# 1.net
KiCad netlist of a schematic drawn in EAGLE
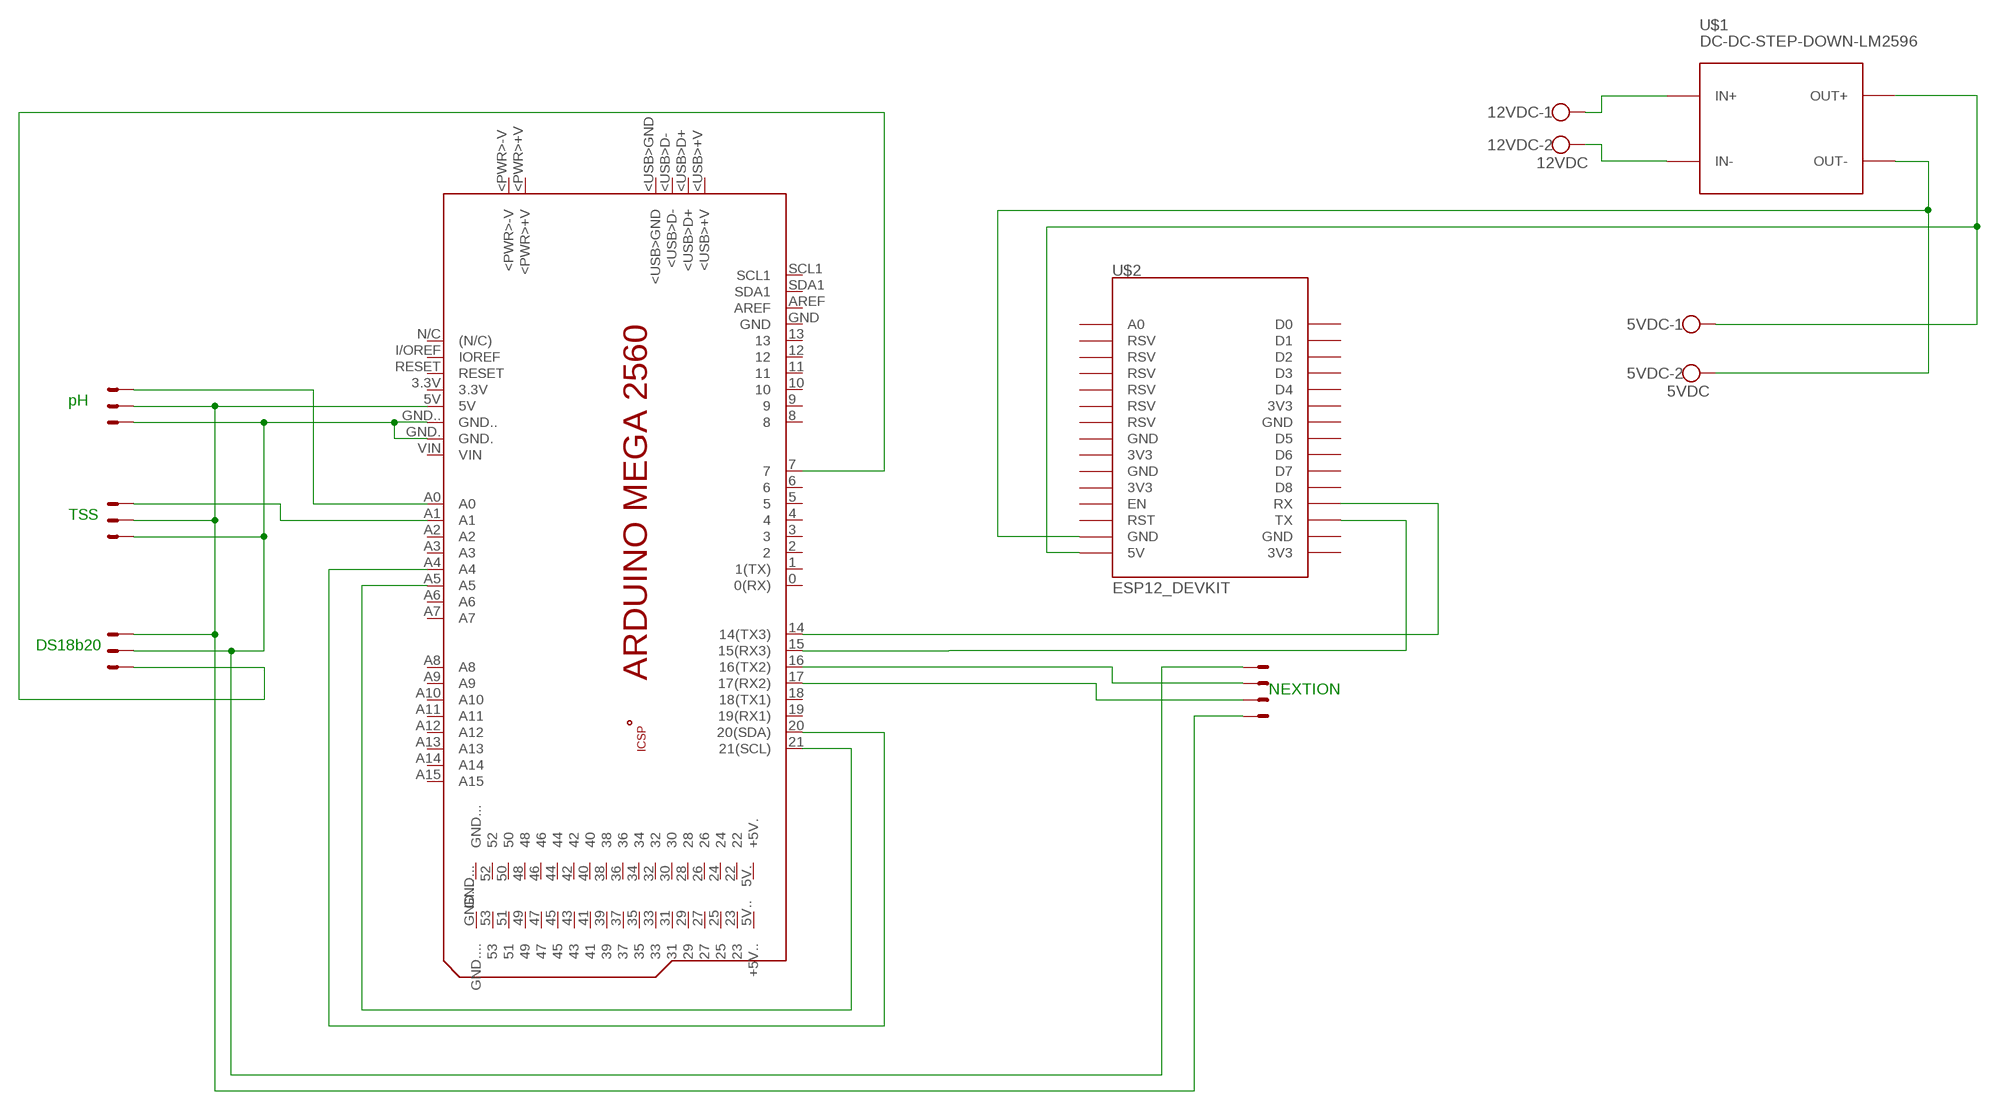
[diagram p0: schematic, sheet 1]

(export (version "E")
  (design (tool "Eeschema 10.0.6"))
  (components
    (comp (ref "5VDC")
      (value "5VDC")
      (footprint "eagle-import:W237-102")
      (fields (field (name "MPN") "237-102"))
      (libsource (lib "eagle-import") (part "W237-102"))
    )
    (comp (ref "12VDC")
      (value "12VDC")
      (footprint "eagle-import:W237-102")
      (fields (field (name "MPN") "237-102"))
      (libsource (lib "eagle-import") (part "W237-102"))
    )
    (comp (ref "A0")
      (value "22-23-2031")
      (footprint "eagle-import:22-23-2031")
      (fields (field (name "MF") "MOLEX"))
      (libsource (lib "eagle-import") (part "22-23-2031"))
    )
    (comp (ref "PCB1")
      (value "ARDUINO_MEGA2560")
      (footprint "eagle-import:ARDUINO_MEGA2560")
      (libsource (lib "eagle-import") (part "ARDUINO_MEGA2560"))
    )
    (comp (ref "U$1")
      (value "DC-DC-STEP-DOWN-LM2596")
      (footprint "eagle-import:DC-DC-STEP-DOWN-LM2596")
      (libsource (lib "eagle-import") (part "DC-DC-STEP-DOWN-LM2596"))
    )
    (comp (ref "U$2")
      (value "ESP12_DEVKIT")
      (footprint "eagle-import:ESP12_DEVKIT")
      (libsource (lib "eagle-import") (part "ESP12_DEVKIT"))
    )
    (comp (ref "X1")
      (value "22-23-2041")
      (footprint "eagle-import:22-23-2041")
      (fields (field (name "MF") "MOLEX"))
      (libsource (lib "eagle-import") (part "22-23-2041"))
    )
    (comp (ref "X2")
      (value "22-23-2031")
      (footprint "eagle-import:22-23-2031")
      (fields (field (name "MF") "MOLEX"))
      (libsource (lib "eagle-import") (part "22-23-2031"))
    )
    (comp (ref "X3")
      (value "22-23-2031")
      (footprint "eagle-import:22-23-2031")
      (fields (field (name "MF") "MOLEX"))
      (libsource (lib "eagle-import") (part "22-23-2031"))
    )
  )
  (nets
    (net (code "1") (name "Net-(5VDCA-KL)") (class "Default")
      (node (ref "5VDC") (pin "1") (pinfunction "KL_1") (pintype "passive"))
      (node (ref "U$1") (pin "OUT+") (pinfunction "OUT+_OUT+") (pintype "bidirectional"))
      (node (ref "U$2") (pin "5V") (pinfunction "5V_5V") (pintype "bidirectional"))
    )
    (net (code "2") (name "Net-(5VDCB-KL)") (class "Default")
      (node (ref "5VDC") (pin "2") (pinfunction "KL_2") (pintype "passive"))
      (node (ref "U$1") (pin "OUT-") (pinfunction "OUT-_OUT-") (pintype "bidirectional"))
      (node (ref "U$2") (pin "GND@1") (pinfunction "GND_GND@1") (pintype "bidirectional"))
    )
    (net (code "3") (name "Net-(12VDCA-KL)") (class "Default")
      (node (ref "12VDC") (pin "1") (pinfunction "KL_1") (pintype "passive"))
      (node (ref "U$1") (pin "IN+") (pinfunction "IN+_IN+") (pintype "bidirectional"))
    )
    (net (code "4") (name "Net-(12VDCB-KL)") (class "Default")
      (node (ref "12VDC") (pin "2") (pinfunction "KL_2") (pintype "passive"))
      (node (ref "U$1") (pin "IN-") (pinfunction "IN-_IN-") (pintype "bidirectional"))
    )
    (net (code "5") (name "Net-(A0A-S)") (class "Default")
      (node (ref "A0") (pin "1") (pinfunction "S_1") (pintype "passive"))
      (node (ref "PCB1") (pin "GND.") (pinfunction "GND._GND.") (pintype "bidirectional"))
      (node (ref "PCB1") (pin "GND..") (pinfunction "GND.._GND..") (pintype "bidirectional"))
      (node (ref "X1") (pin "1") (pinfunction "S_1") (pintype "passive"))
      (node (ref "X2") (pin "1") (pinfunction "S_1") (pintype "passive"))
      (node (ref "X3") (pin "2") (pinfunction "S_2") (pintype "passive"))
    )
    (net (code "6") (name "Net-(A0B-S)") (class "Default")
      (node (ref "A0") (pin "2") (pinfunction "S_2") (pintype "passive"))
      (node (ref "PCB1") (pin "5V") (pinfunction "5V_5V") (pintype "bidirectional"))
      (node (ref "X1") (pin "4") (pinfunction "S_4") (pintype "passive"))
      (node (ref "X2") (pin "2") (pinfunction "S_2") (pintype "passive"))
      (node (ref "X3") (pin "3") (pinfunction "S_3") (pintype "passive"))
    )
    (net (code "7") (name "Net-(A0C-S)") (class "Default")
      (node (ref "A0") (pin "3") (pinfunction "S_3") (pintype "passive"))
      (node (ref "PCB1") (pin "A0") (pinfunction "A0_A0") (pintype "bidirectional"))
    )
    (net (code "8") (name "Net-(PCB1-14(TX3))") (class "Default")
      (node (ref "PCB1") (pin "14") (pinfunction "14(TX3)_14") (pintype "bidirectional"))
      (node (ref "U$2") (pin "RX") (pinfunction "RX_RX") (pintype "bidirectional"))
    )
    (net (code "9") (name "Net-(PCB1-15(RX3))") (class "Default")
      (node (ref "PCB1") (pin "15") (pinfunction "15(RX3)_15") (pintype "bidirectional"))
      (node (ref "U$2") (pin "TX") (pinfunction "TX_TX") (pintype "bidirectional"))
    )
    (net (code "10") (name "Net-(PCB1-16(TX2))") (class "Default")
      (node (ref "PCB1") (pin "16") (pinfunction "16(TX2)_16") (pintype "bidirectional"))
      (node (ref "X1") (pin "2") (pinfunction "S_2") (pintype "passive"))
    )
    (net (code "11") (name "Net-(PCB1-17(RX2))") (class "Default")
      (node (ref "PCB1") (pin "17") (pinfunction "17(RX2)_17") (pintype "bidirectional"))
      (node (ref "X1") (pin "3") (pinfunction "S_3") (pintype "passive"))
    )
    (net (code "12") (name "Net-(PCB1-20(SDA))") (class "Default")
      (node (ref "PCB1") (pin "20") (pinfunction "20(SDA)_20") (pintype "bidirectional"))
      (node (ref "PCB1") (pin "A4") (pinfunction "A4_A4") (pintype "bidirectional"))
    )
    (net (code "13") (name "Net-(PCB1-21(SCL))") (class "Default")
      (node (ref "PCB1") (pin "21") (pinfunction "21(SCL)_21") (pintype "bidirectional"))
      (node (ref "PCB1") (pin "A5") (pinfunction "A5_A5") (pintype "bidirectional"))
    )
    (net (code "14") (name "Net-(X2C-S)") (class "Default")
      (node (ref "PCB1") (pin "A1") (pinfunction "A1_A1") (pintype "bidirectional"))
      (node (ref "X2") (pin "3") (pinfunction "S_3") (pintype "passive"))
    )
    (net (code "15") (name "Net-(X3A-S)") (class "Default")
      (node (ref "PCB1") (pin "7") (pinfunction "7_7") (pintype "bidirectional"))
      (node (ref "X3") (pin "1") (pinfunction "S_1") (pintype "passive"))
    )
    (net (code "16") (name "unconnected-(PCB1-(N{slash}C)-PadN{slash}C)") (class "Default")
      (node (ref "PCB1") (pin "N/C") (pinfunction "(N/C)_N/C") (pintype "bidirectional"))
    )
    (net (code "17") (name "unconnected-(PCB1-+5V.-Pad5V.)") (class "Default")
      (node (ref "PCB1") (pin "5V.") (pinfunction "+5V._5V.") (pintype "bidirectional"))
    )
    (net (code "18") (name "unconnected-(PCB1-+5V..-Pad5V..)") (class "Default")
      (node (ref "PCB1") (pin "5V..") (pinfunction "+5V.._5V..") (pintype "bidirectional"))
    )
    (net (code "19") (name "unconnected-(PCB1-0(RX)-Pad0)") (class "Default")
      (node (ref "PCB1") (pin "0") (pinfunction "0(RX)_0") (pintype "bidirectional"))
    )
    (net (code "20") (name "unconnected-(PCB1-1(TX)-Pad1)") (class "Default")
      (node (ref "PCB1") (pin "1") (pinfunction "1(TX)_1") (pintype "bidirectional"))
    )
    (net (code "21") (name "unconnected-(PCB1-18(TX1)-Pad18)") (class "Default")
      (node (ref "PCB1") (pin "18") (pinfunction "18(TX1)_18") (pintype "bidirectional"))
    )
    (net (code "22") (name "unconnected-(PCB1-19(RX1)-Pad19)") (class "Default")
      (node (ref "PCB1") (pin "19") (pinfunction "19(RX1)_19") (pintype "bidirectional"))
    )
    (net (code "23") (name "unconnected-(PCB1-IOREF-PadI{slash}OREF)") (class "Default")
      (node (ref "PCB1") (pin "I/OREF") (pinfunction "IOREF_I/OREF") (pintype "bidirectional"))
    )
    (net (code "24") (name "unconnected-(PCB1-Pad+5V_)") (class "Default")
      (node (ref "PCB1") (pin "+5V_") (pinfunction "+5V__+5V_") (pintype "bidirectional"))
    )
    (net (code "25") (name "unconnected-(PCB1-Pad2)") (class "Default")
      (node (ref "PCB1") (pin "2") (pinfunction "2_2") (pintype "bidirectional"))
    )
    (net (code "26") (name "unconnected-(PCB1-Pad3)") (class "Default")
      (node (ref "PCB1") (pin "3") (pinfunction "3_3") (pintype "bidirectional"))
    )
    (net (code "27") (name "unconnected-(PCB1-Pad3.3V)") (class "Default")
      (node (ref "PCB1") (pin "3.3V") (pinfunction "3.3V_3.3V") (pintype "bidirectional"))
    )
    (net (code "28") (name "unconnected-(PCB1-Pad4)") (class "Default")
      (node (ref "PCB1") (pin "4") (pinfunction "4_4") (pintype "bidirectional"))
    )
    (net (code "29") (name "unconnected-(PCB1-Pad5)") (class "Default")
      (node (ref "PCB1") (pin "5") (pinfunction "5_5") (pintype "bidirectional"))
    )
    (net (code "30") (name "unconnected-(PCB1-Pad6)") (class "Default")
      (node (ref "PCB1") (pin "6") (pinfunction "6_6") (pintype "bidirectional"))
    )
    (net (code "31") (name "unconnected-(PCB1-Pad8)") (class "Default")
      (node (ref "PCB1") (pin "8") (pinfunction "8_8") (pintype "bidirectional"))
    )
    (net (code "32") (name "unconnected-(PCB1-Pad9)") (class "Default")
      (node (ref "PCB1") (pin "9") (pinfunction "9_9") (pintype "bidirectional"))
    )
    (net (code "33") (name "unconnected-(PCB1-Pad10)") (class "Default")
      (node (ref "PCB1") (pin "10") (pinfunction "10_10") (pintype "bidirectional"))
    )
    (net (code "34") (name "unconnected-(PCB1-Pad11)") (class "Default")
      (node (ref "PCB1") (pin "11") (pinfunction "11_11") (pintype "bidirectional"))
    )
    (net (code "35") (name "unconnected-(PCB1-Pad12)") (class "Default")
      (node (ref "PCB1") (pin "12") (pinfunction "12_12") (pintype "bidirectional"))
    )
    (net (code "36") (name "unconnected-(PCB1-Pad13)") (class "Default")
      (node (ref "PCB1") (pin "13") (pinfunction "13_13") (pintype "bidirectional"))
    )
    (net (code "37") (name "unconnected-(PCB1-Pad22)") (class "Default")
      (node (ref "PCB1") (pin "22") (pinfunction "22_22") (pintype "bidirectional"))
    )
    (net (code "38") (name "unconnected-(PCB1-Pad23)") (class "Default")
      (node (ref "PCB1") (pin "23") (pinfunction "23_23") (pintype "bidirectional"))
    )
    (net (code "39") (name "unconnected-(PCB1-Pad24)") (class "Default")
      (node (ref "PCB1") (pin "24") (pinfunction "24_24") (pintype "bidirectional"))
    )
    (net (code "40") (name "unconnected-(PCB1-Pad25)") (class "Default")
      (node (ref "PCB1") (pin "25") (pinfunction "25_25") (pintype "bidirectional"))
    )
    (net (code "41") (name "unconnected-(PCB1-Pad26)") (class "Default")
      (node (ref "PCB1") (pin "26") (pinfunction "26_26") (pintype "bidirectional"))
    )
    (net (code "42") (name "unconnected-(PCB1-Pad27)") (class "Default")
      (node (ref "PCB1") (pin "27") (pinfunction "27_27") (pintype "bidirectional"))
    )
    (net (code "43") (name "unconnected-(PCB1-Pad28)") (class "Default")
      (node (ref "PCB1") (pin "28") (pinfunction "28_28") (pintype "bidirectional"))
    )
    (net (code "44") (name "unconnected-(PCB1-Pad29)") (class "Default")
      (node (ref "PCB1") (pin "29") (pinfunction "29_29") (pintype "bidirectional"))
    )
    (net (code "45") (name "unconnected-(PCB1-Pad30)") (class "Default")
      (node (ref "PCB1") (pin "30") (pinfunction "30_30") (pintype "bidirectional"))
    )
    (net (code "46") (name "unconnected-(PCB1-Pad31)") (class "Default")
      (node (ref "PCB1") (pin "31") (pinfunction "31_31") (pintype "bidirectional"))
    )
    (net (code "47") (name "unconnected-(PCB1-Pad32)") (class "Default")
      (node (ref "PCB1") (pin "32") (pinfunction "32_32") (pintype "bidirectional"))
    )
    (net (code "48") (name "unconnected-(PCB1-Pad33)") (class "Default")
      (node (ref "PCB1") (pin "33") (pinfunction "33_33") (pintype "bidirectional"))
    )
    (net (code "49") (name "unconnected-(PCB1-Pad34)") (class "Default")
      (node (ref "PCB1") (pin "34") (pinfunction "34_34") (pintype "bidirectional"))
    )
    (net (code "50") (name "unconnected-(PCB1-Pad35)") (class "Default")
      (node (ref "PCB1") (pin "35") (pinfunction "35_35") (pintype "bidirectional"))
    )
    (net (code "51") (name "unconnected-(PCB1-Pad36)") (class "Default")
      (node (ref "PCB1") (pin "36") (pinfunction "36_36") (pintype "bidirectional"))
    )
    (net (code "52") (name "unconnected-(PCB1-Pad37)") (class "Default")
      (node (ref "PCB1") (pin "37") (pinfunction "37_37") (pintype "bidirectional"))
    )
    (net (code "53") (name "unconnected-(PCB1-Pad38)") (class "Default")
      (node (ref "PCB1") (pin "38") (pinfunction "38_38") (pintype "bidirectional"))
    )
    (net (code "54") (name "unconnected-(PCB1-Pad39)") (class "Default")
      (node (ref "PCB1") (pin "39") (pinfunction "39_39") (pintype "bidirectional"))
    )
    (net (code "55") (name "unconnected-(PCB1-Pad40)") (class "Default")
      (node (ref "PCB1") (pin "40") (pinfunction "40_40") (pintype "bidirectional"))
    )
    (net (code "56") (name "unconnected-(PCB1-Pad41)") (class "Default")
      (node (ref "PCB1") (pin "41") (pinfunction "41_41") (pintype "bidirectional"))
    )
    (net (code "57") (name "unconnected-(PCB1-Pad42)") (class "Default")
      (node (ref "PCB1") (pin "42") (pinfunction "42_42") (pintype "bidirectional"))
    )
    (net (code "58") (name "unconnected-(PCB1-Pad43)") (class "Default")
      (node (ref "PCB1") (pin "43") (pinfunction "43_43") (pintype "bidirectional"))
    )
    (net (code "59") (name "unconnected-(PCB1-Pad44)") (class "Default")
      (node (ref "PCB1") (pin "44") (pinfunction "44_44") (pintype "bidirectional"))
    )
    (net (code "60") (name "unconnected-(PCB1-Pad45)") (class "Default")
      (node (ref "PCB1") (pin "45") (pinfunction "45_45") (pintype "bidirectional"))
    )
    (net (code "61") (name "unconnected-(PCB1-Pad46)") (class "Default")
      (node (ref "PCB1") (pin "46") (pinfunction "46_46") (pintype "bidirectional"))
    )
    (net (code "62") (name "unconnected-(PCB1-Pad47)") (class "Default")
      (node (ref "PCB1") (pin "47") (pinfunction "47_47") (pintype "bidirectional"))
    )
    (net (code "63") (name "unconnected-(PCB1-Pad48)") (class "Default")
      (node (ref "PCB1") (pin "48") (pinfunction "48_48") (pintype "bidirectional"))
    )
    (net (code "64") (name "unconnected-(PCB1-Pad49)") (class "Default")
      (node (ref "PCB1") (pin "49") (pinfunction "49_49") (pintype "bidirectional"))
    )
    (net (code "65") (name "unconnected-(PCB1-Pad50)") (class "Default")
      (node (ref "PCB1") (pin "50") (pinfunction "50_50") (pintype "bidirectional"))
    )
    (net (code "66") (name "unconnected-(PCB1-Pad51)") (class "Default")
      (node (ref "PCB1") (pin "51") (pinfunction "51_51") (pintype "bidirectional"))
    )
    (net (code "67") (name "unconnected-(PCB1-Pad52)") (class "Default")
      (node (ref "PCB1") (pin "52") (pinfunction "52_52") (pintype "bidirectional"))
    )
    (net (code "68") (name "unconnected-(PCB1-Pad53)") (class "Default")
      (node (ref "PCB1") (pin "53") (pinfunction "53_53") (pintype "bidirectional"))
    )
    (net (code "69") (name "unconnected-(PCB1-Pad<PWR>+V)") (class "Default")
      (node (ref "PCB1") (pin "<PWR>+V") (pinfunction "<PWR>+V_<PWR>+V") (pintype "no_connect"))
    )
    (net (code "70") (name "unconnected-(PCB1-Pad<PWR>-V)") (class "Default")
      (node (ref "PCB1") (pin "<PWR>-V") (pinfunction "<PWR>-V_<PWR>-V") (pintype "no_connect"))
    )
    (net (code "71") (name "unconnected-(PCB1-Pad<USB>+V)") (class "Default")
      (node (ref "PCB1") (pin "<USB>+V") (pinfunction "<USB>+V_<USB>+V") (pintype "no_connect"))
    )
    (net (code "72") (name "unconnected-(PCB1-Pad<USB>D+)") (class "Default")
      (node (ref "PCB1") (pin "<USB>D+") (pinfunction "<USB>D+_<USB>D+") (pintype "no_connect"))
    )
    (net (code "73") (name "unconnected-(PCB1-Pad<USB>D-)") (class "Default")
      (node (ref "PCB1") (pin "<USB>D-") (pinfunction "<USB>D-_<USB>D-") (pintype "no_connect"))
    )
    (net (code "74") (name "unconnected-(PCB1-Pad<USB>GND)") (class "Default")
      (node (ref "PCB1") (pin "<USB>GND") (pinfunction "<USB>GND_<USB>GND") (pintype "no_connect"))
    )
    (net (code "75") (name "unconnected-(PCB1-PadA2)") (class "Default")
      (node (ref "PCB1") (pin "A2") (pinfunction "A2_A2") (pintype "bidirectional"))
    )
    (net (code "76") (name "unconnected-(PCB1-PadA3)") (class "Default")
      (node (ref "PCB1") (pin "A3") (pinfunction "A3_A3") (pintype "bidirectional"))
    )
    (net (code "77") (name "unconnected-(PCB1-PadA6)") (class "Default")
      (node (ref "PCB1") (pin "A6") (pinfunction "A6_A6") (pintype "bidirectional"))
    )
    (net (code "78") (name "unconnected-(PCB1-PadA7)") (class "Default")
      (node (ref "PCB1") (pin "A7") (pinfunction "A7_A7") (pintype "bidirectional"))
    )
    (net (code "79") (name "unconnected-(PCB1-PadA8)") (class "Default")
      (node (ref "PCB1") (pin "A8") (pinfunction "A8_A8") (pintype "bidirectional"))
    )
    (net (code "80") (name "unconnected-(PCB1-PadA9)") (class "Default")
      (node (ref "PCB1") (pin "A9") (pinfunction "A9_A9") (pintype "bidirectional"))
    )
    (net (code "81") (name "unconnected-(PCB1-PadA10)") (class "Default")
      (node (ref "PCB1") (pin "A10") (pinfunction "A10_A10") (pintype "bidirectional"))
    )
    (net (code "82") (name "unconnected-(PCB1-PadA11)") (class "Default")
      (node (ref "PCB1") (pin "A11") (pinfunction "A11_A11") (pintype "bidirectional"))
    )
    (net (code "83") (name "unconnected-(PCB1-PadA12)") (class "Default")
      (node (ref "PCB1") (pin "A12") (pinfunction "A12_A12") (pintype "bidirectional"))
    )
    (net (code "84") (name "unconnected-(PCB1-PadA13)") (class "Default")
      (node (ref "PCB1") (pin "A13") (pinfunction "A13_A13") (pintype "bidirectional"))
    )
    (net (code "85") (name "unconnected-(PCB1-PadA14)") (class "Default")
      (node (ref "PCB1") (pin "A14") (pinfunction "A14_A14") (pintype "bidirectional"))
    )
    (net (code "86") (name "unconnected-(PCB1-PadA15)") (class "Default")
      (node (ref "PCB1") (pin "A15") (pinfunction "A15_A15") (pintype "bidirectional"))
    )
    (net (code "87") (name "unconnected-(PCB1-PadAREF)") (class "Default")
      (node (ref "PCB1") (pin "AREF") (pinfunction "AREF_AREF") (pintype "bidirectional"))
    )
    (net (code "88") (name "unconnected-(PCB1-PadGND)") (class "Default")
      (node (ref "PCB1") (pin "GND") (pinfunction "GND_GND") (pintype "bidirectional"))
    )
    (net (code "89") (name "unconnected-(PCB1-PadGND...)") (class "Default")
      (node (ref "PCB1") (pin "GND...") (pinfunction "GND..._GND...") (pintype "bidirectional"))
    )
    (net (code "90") (name "unconnected-(PCB1-PadGND....)") (class "Default")
      (node (ref "PCB1") (pin "GND....") (pinfunction "GND...._GND....") (pintype "bidirectional"))
    )
    (net (code "91") (name "unconnected-(PCB1-PadGND__)") (class "Default")
      (node (ref "PCB1") (pin "GND__") (pinfunction "GND___GND__") (pintype "bidirectional"))
    )
    (net (code "92") (name "unconnected-(PCB1-PadMISO)") (class "Default")
      (node (ref "PCB1") (pin "MISO") (pinfunction "MISO_MISO") (pintype "bidirectional"))
    )
    (net (code "93") (name "unconnected-(PCB1-PadMOSI)") (class "Default")
      (node (ref "PCB1") (pin "MOSI") (pinfunction "MOSI_MOSI") (pintype "bidirectional"))
    )
    (net (code "94") (name "unconnected-(PCB1-PadRESET)") (class "Default")
      (node (ref "PCB1") (pin "RESET") (pinfunction "RESET_RESET") (pintype "bidirectional"))
    )
    (net (code "95") (name "unconnected-(PCB1-PadRESET.)") (class "Default")
      (node (ref "PCB1") (pin "RESET.") (pinfunction "RESET._RESET.") (pintype "bidirectional"))
    )
    (net (code "96") (name "unconnected-(PCB1-PadSCK)") (class "Default")
      (node (ref "PCB1") (pin "SCK") (pinfunction "SCK_SCK") (pintype "bidirectional"))
    )
    (net (code "97") (name "unconnected-(PCB1-PadSCL1)") (class "Default")
      (node (ref "PCB1") (pin "SCL1") (pinfunction "SCL1_SCL1") (pintype "bidirectional"))
    )
    (net (code "98") (name "unconnected-(PCB1-PadSDA1)") (class "Default")
      (node (ref "PCB1") (pin "SDA1") (pinfunction "SDA1_SDA1") (pintype "bidirectional"))
    )
    (net (code "99") (name "unconnected-(PCB1-PadVIN)") (class "Default")
      (node (ref "PCB1") (pin "VIN") (pinfunction "VIN_VIN") (pintype "bidirectional"))
    )
    (net (code "100") (name "unconnected-(U$2-3V3-Pad3V3@0)") (class "Default")
      (node (ref "U$2") (pin "3V3@0") (pinfunction "3V3_3V3@0") (pintype "bidirectional"))
    )
    (net (code "101") (name "unconnected-(U$2-3V3-Pad3V3@1)") (class "Default")
      (node (ref "U$2") (pin "3V3@1") (pinfunction "3V3_3V3@1") (pintype "bidirectional"))
    )
    (net (code "102") (name "unconnected-(U$2-3V3-Pad3V3@2)") (class "Default")
      (node (ref "U$2") (pin "3V3@2") (pinfunction "3V3_3V3@2") (pintype "bidirectional"))
    )
    (net (code "103") (name "unconnected-(U$2-3V3-Pad3V3@3)") (class "Default")
      (node (ref "U$2") (pin "3V3@3") (pinfunction "3V3_3V3@3") (pintype "bidirectional"))
    )
    (net (code "104") (name "unconnected-(U$2-GND-PadGND@0)") (class "Default")
      (node (ref "U$2") (pin "GND@0") (pinfunction "GND_GND@0") (pintype "bidirectional"))
    )
    (net (code "105") (name "unconnected-(U$2-GND-PadGND@2)") (class "Default")
      (node (ref "U$2") (pin "GND@2") (pinfunction "GND_GND@2") (pintype "bidirectional"))
    )
    (net (code "106") (name "unconnected-(U$2-GND-PadGND@3)") (class "Default")
      (node (ref "U$2") (pin "GND@3") (pinfunction "GND_GND@3") (pintype "bidirectional"))
    )
    (net (code "107") (name "unconnected-(U$2-GND-PadGND@4)") (class "Default")
      (node (ref "U$2") (pin "GND@4") (pinfunction "GND_GND@4") (pintype "bidirectional"))
    )
    (net (code "108") (name "unconnected-(U$2-PadA0)") (class "Default")
      (node (ref "U$2") (pin "A0") (pinfunction "A0_A0") (pintype "bidirectional"))
    )
    (net (code "109") (name "unconnected-(U$2-PadD0)") (class "Default")
      (node (ref "U$2") (pin "D0") (pinfunction "D0_D0") (pintype "bidirectional"))
    )
    (net (code "110") (name "unconnected-(U$2-PadD1)") (class "Default")
      (node (ref "U$2") (pin "D1") (pinfunction "D1_D1") (pintype "bidirectional"))
    )
    (net (code "111") (name "unconnected-(U$2-PadD2)") (class "Default")
      (node (ref "U$2") (pin "D2") (pinfunction "D2_D2") (pintype "bidirectional"))
    )
    (net (code "112") (name "unconnected-(U$2-PadD3)") (class "Default")
      (node (ref "U$2") (pin "D3") (pinfunction "D3_D3") (pintype "bidirectional"))
    )
    (net (code "113") (name "unconnected-(U$2-PadD4)") (class "Default")
      (node (ref "U$2") (pin "D4") (pinfunction "D4_D4") (pintype "bidirectional"))
    )
    (net (code "114") (name "unconnected-(U$2-PadD5)") (class "Default")
      (node (ref "U$2") (pin "D5") (pinfunction "D5_D5") (pintype "bidirectional"))
    )
    (net (code "115") (name "unconnected-(U$2-PadD6)") (class "Default")
      (node (ref "U$2") (pin "D6") (pinfunction "D6_D6") (pintype "bidirectional"))
    )
    (net (code "116") (name "unconnected-(U$2-PadD7)") (class "Default")
      (node (ref "U$2") (pin "D7") (pinfunction "D7_D7") (pintype "bidirectional"))
    )
    (net (code "117") (name "unconnected-(U$2-PadD8)") (class "Default")
      (node (ref "U$2") (pin "D8") (pinfunction "D8_D8") (pintype "bidirectional"))
    )
    (net (code "118") (name "unconnected-(U$2-PadEN)") (class "Default")
      (node (ref "U$2") (pin "EN") (pinfunction "EN_EN") (pintype "bidirectional"))
    )
    (net (code "119") (name "unconnected-(U$2-PadRST)") (class "Default")
      (node (ref "U$2") (pin "RST") (pinfunction "RST_RST") (pintype "bidirectional"))
    )
    (net (code "120") (name "unconnected-(U$2-RSV-PadRSV@0)") (class "Default")
      (node (ref "U$2") (pin "RSV@0") (pinfunction "RSV_RSV@0") (pintype "bidirectional"))
    )
    (net (code "121") (name "unconnected-(U$2-RSV-PadRSV@1)") (class "Default")
      (node (ref "U$2") (pin "RSV@1") (pinfunction "RSV_RSV@1") (pintype "bidirectional"))
    )
    (net (code "122") (name "unconnected-(U$2-RSV-PadRSV@2)") (class "Default")
      (node (ref "U$2") (pin "RSV@2") (pinfunction "RSV_RSV@2") (pintype "bidirectional"))
    )
    (net (code "123") (name "unconnected-(U$2-RSV-PadRSV@3)") (class "Default")
      (node (ref "U$2") (pin "RSV@3") (pinfunction "RSV_RSV@3") (pintype "bidirectional"))
    )
    (net (code "124") (name "unconnected-(U$2-RSV-PadRSV@4)") (class "Default")
      (node (ref "U$2") (pin "RSV@4") (pinfunction "RSV_RSV@4") (pintype "bidirectional"))
    )
    (net (code "125") (name "unconnected-(U$2-RSV-PadRSV@5)") (class "Default")
      (node (ref "U$2") (pin "RSV@5") (pinfunction "RSV_RSV@5") (pintype "bidirectional"))
    )
  )
)
